# lcd_keyb.net
KiCad netlist of a schematic drawn in Altium Designer
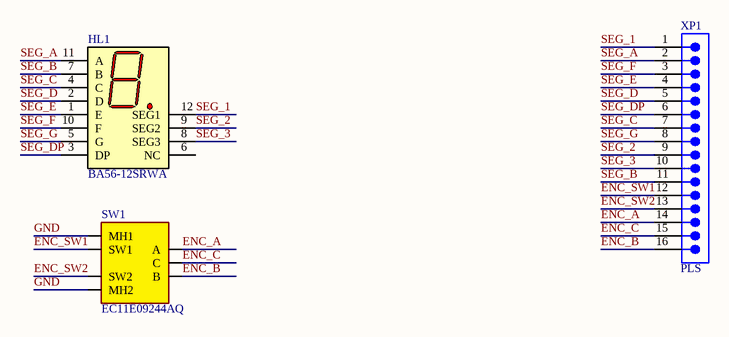
[diagram p0: lcd_keyb.SchDoc]

(export (version "E")
  (design (tool "Eeschema 10.0.6"))
  (components
    (comp (ref "HL1")
      (value "BA56-12SRWA")
      (footprint "BX56-12")
      (libsource (lib "Optoelectronics") (part "BX56-12"))
    )
    (comp (ref "SW1")
      (value "EC11E09244AQ")
      (footprint "EC11E09244AQ")
      (libsource (lib "Button") (part "RotaryEncoder"))
    )
    (comp (ref "XP1")
      (value "PLS")
      (footprint "PLS-16R")
      (fields (field (name "PART NUMBER") "PLS-16R"))
      (libsource (lib "Connector") (part "CN_16P_1W"))
    )
  )
  (nets
    (net (code "1") (name "/ENC_A") (class "Default")
      (node (ref "SW1") (pin "A") (pinfunction "A_A") (pintype "passive"))
      (node (ref "XP1") (pin "14") (pinfunction "14_14") (pintype "passive"))
    )
    (net (code "2") (name "/ENC_B") (class "Default")
      (node (ref "SW1") (pin "B") (pinfunction "B_B") (pintype "passive"))
      (node (ref "XP1") (pin "16") (pinfunction "16_16") (pintype "passive"))
    )
    (net (code "3") (name "/ENC_C") (class "Default")
      (node (ref "SW1") (pin "C") (pinfunction "C_C") (pintype "passive"))
      (node (ref "XP1") (pin "15") (pinfunction "15_15") (pintype "passive"))
    )
    (net (code "4") (name "/ENC_SW1") (class "Default")
      (node (ref "SW1") (pin "SW1") (pinfunction "SW1_SW1") (pintype "passive"))
      (node (ref "XP1") (pin "12") (pinfunction "12_12") (pintype "passive"))
    )
    (net (code "5") (name "/ENC_SW2") (class "Default")
      (node (ref "SW1") (pin "SW2") (pinfunction "SW2_SW2") (pintype "passive"))
      (node (ref "XP1") (pin "13") (pinfunction "13_13") (pintype "passive"))
    )
    (net (code "6") (name "/GND") (class "Default")
      (node (ref "SW1") (pin "MH1") (pinfunction "MH1_MH1") (pintype "passive"))
      (node (ref "SW1") (pin "MH2") (pinfunction "MH2_MH2") (pintype "passive"))
    )
    (net (code "7") (name "/SEG_1") (class "Default")
      (node (ref "HL1") (pin "12") (pinfunction "SEG1_12") (pintype "passive"))
      (node (ref "XP1") (pin "1") (pinfunction "1_1") (pintype "passive"))
    )
    (net (code "8") (name "/SEG_2") (class "Default")
      (node (ref "HL1") (pin "9") (pinfunction "SEG2_9") (pintype "passive"))
      (node (ref "XP1") (pin "9") (pinfunction "9_9") (pintype "passive"))
    )
    (net (code "9") (name "/SEG_3") (class "Default")
      (node (ref "HL1") (pin "8") (pinfunction "SEG3_8") (pintype "passive"))
      (node (ref "XP1") (pin "10") (pinfunction "10_10") (pintype "passive"))
    )
    (net (code "10") (name "/SEG_A") (class "Default")
      (node (ref "HL1") (pin "11") (pinfunction "A_11") (pintype "passive"))
      (node (ref "XP1") (pin "2") (pinfunction "2_2") (pintype "passive"))
    )
    (net (code "11") (name "/SEG_B") (class "Default")
      (node (ref "HL1") (pin "7") (pinfunction "B_7") (pintype "passive"))
      (node (ref "XP1") (pin "11") (pinfunction "11_11") (pintype "passive"))
    )
    (net (code "12") (name "/SEG_C") (class "Default")
      (node (ref "HL1") (pin "4") (pinfunction "C_4") (pintype "passive"))
      (node (ref "XP1") (pin "7") (pinfunction "7_7") (pintype "passive"))
    )
    (net (code "13") (name "/SEG_D") (class "Default")
      (node (ref "HL1") (pin "2") (pinfunction "D_2") (pintype "passive"))
      (node (ref "XP1") (pin "5") (pinfunction "5_5") (pintype "passive"))
    )
    (net (code "14") (name "/SEG_DP") (class "Default")
      (node (ref "HL1") (pin "3") (pinfunction "DP_3") (pintype "passive"))
      (node (ref "XP1") (pin "6") (pinfunction "6_6") (pintype "passive"))
    )
    (net (code "15") (name "/SEG_E") (class "Default")
      (node (ref "HL1") (pin "1") (pinfunction "E_1") (pintype "passive"))
      (node (ref "XP1") (pin "4") (pinfunction "4_4") (pintype "passive"))
    )
    (net (code "16") (name "/SEG_F") (class "Default")
      (node (ref "HL1") (pin "10") (pinfunction "F_10") (pintype "passive"))
      (node (ref "XP1") (pin "3") (pinfunction "3_3") (pintype "passive"))
    )
    (net (code "17") (name "/SEG_G") (class "Default")
      (node (ref "HL1") (pin "5") (pinfunction "G_5") (pintype "passive"))
      (node (ref "XP1") (pin "8") (pinfunction "8_8") (pintype "passive"))
    )
    (net (code "18") (name "unconnected-(HL1-NC-Pad6)") (class "Default")
      (node (ref "HL1") (pin "6") (pinfunction "NC_6") (pintype "passive"))
    )
  )
)
